# h2oiq_v4.net
KiCad netlist of a schematic drawn in EAGLE
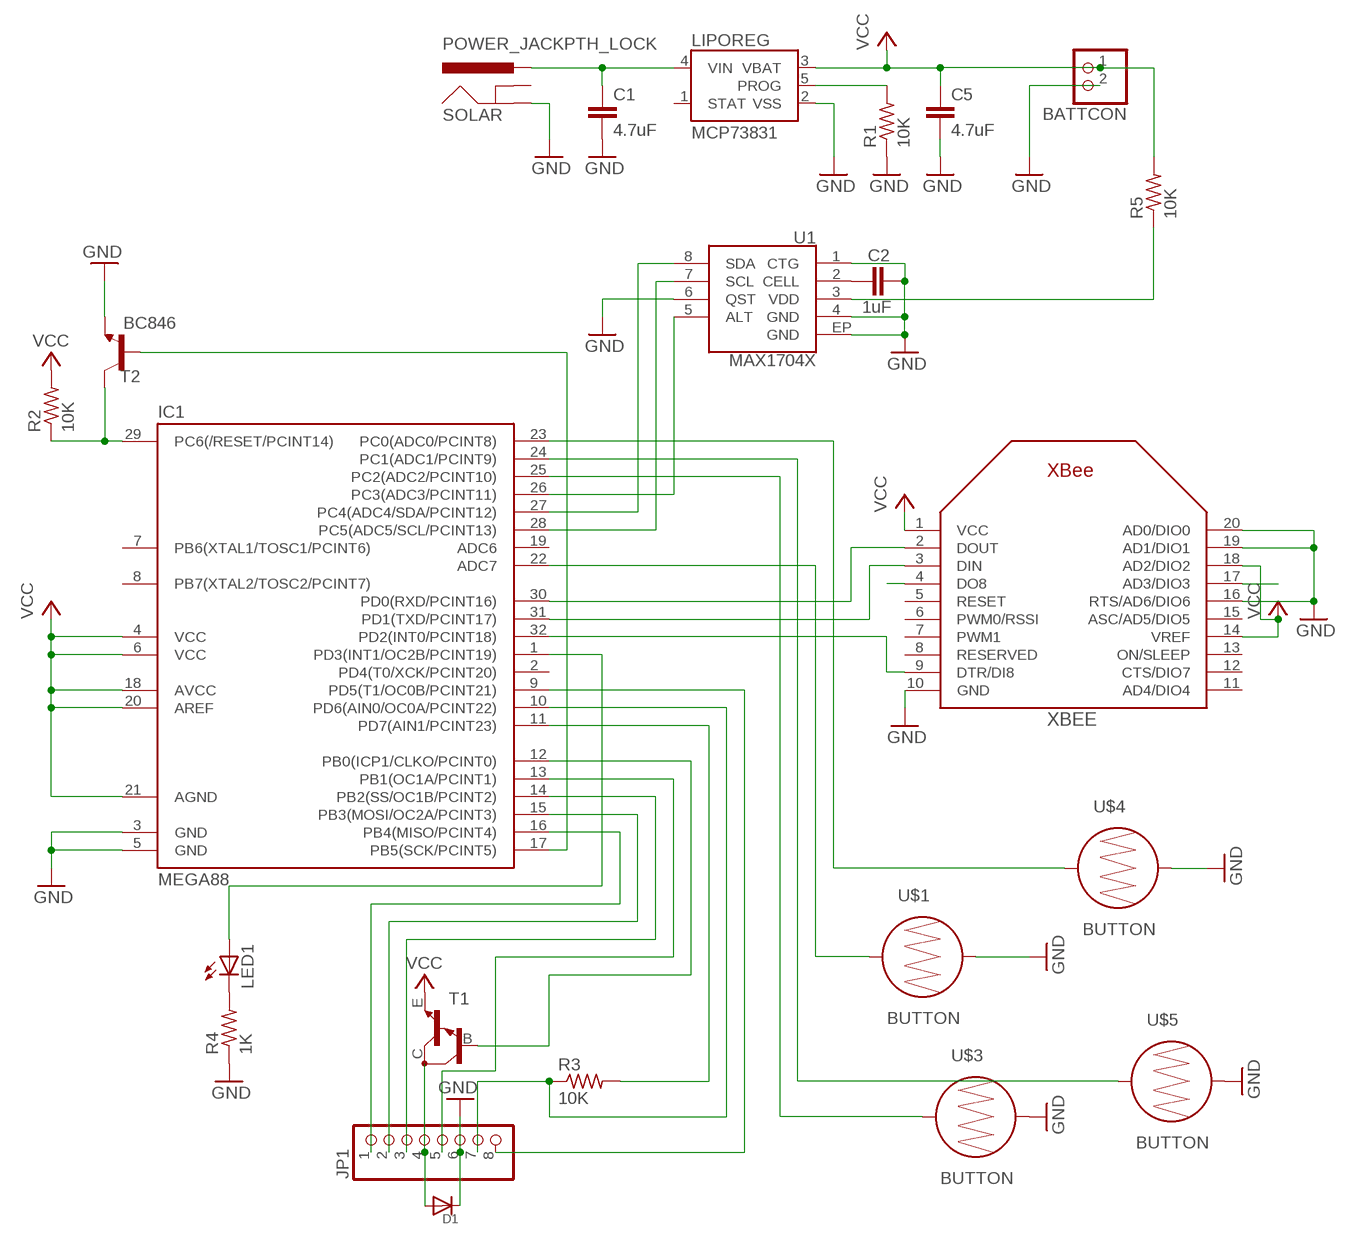
[diagram p0: schematic, sheet 1]

(export (version "E")
  (design (tool "Eeschema 10.0.6"))
  (components
    (comp (ref "BATTCON")
      (value "JST_2PIN-SMT")
      (footprint "eagle-import:JST-PH-2-SMT")
      (libsource (lib "eagle-import") (part "JST_2PIN-SMT"))
    )
    (comp (ref "C1")
      (value "4.7uF")
      (footprint "eagle-import:0402-CAP")
      (libsource (lib "eagle-import") (part "CAP0402-CAP"))
    )
    (comp (ref "C2")
      (value "1uF")
      (footprint "eagle-import:0402-CAP")
      (libsource (lib "eagle-import") (part "CAP0402-CAP"))
    )
    (comp (ref "C5")
      (value "4.7uF")
      (footprint "eagle-import:0402-CAP")
      (libsource (lib "eagle-import") (part "CAP0402-CAP"))
    )
    (comp (ref "D1")
      (value "DIODESMA")
      (footprint "eagle-import:SMADIODE")
      (libsource (lib "eagle-import") (part "DIODESMA"))
    )
    (comp (ref "IC1")
      (value "MEGA88")
      (footprint "eagle-import:MLF32")
      (libsource (lib "eagle-import") (part "MEGA48/88/168-MU"))
    )
    (comp (ref "JP1")
      (value "PINHD-1X8LOCK")
      (footprint "eagle-import:1X08-LOCK")
      (libsource (lib "eagle-import") (part "PINHD-1X8LOCK"))
    )
    (comp (ref "LED1")
      (value "LED")
      (footprint "eagle-import:SMARTLED-TTW")
      (libsource (lib "eagle-import") (part "LED"))
    )
    (comp (ref "LIPOREG")
      (value "MCP73831")
      (footprint "eagle-import:SOT23-5")
      (libsource (lib "eagle-import") (part "MCP73831"))
    )
    (comp (ref "R1")
      (value "10K")
      (footprint "eagle-import:R0603")
      (libsource (lib "eagle-import") (part "resistor_R-US_R0603"))
    )
    (comp (ref "R2")
      (value "10K")
      (footprint "eagle-import:R0603@1")
      (libsource (lib "eagle-import") (part "R-US_R0603"))
    )
    (comp (ref "R3")
      (value "10K")
      (footprint "eagle-import:R0603")
      (libsource (lib "eagle-import") (part "resistor_R-US_R0603"))
    )
    (comp (ref "R4")
      (value "1K")
      (footprint "eagle-import:R0603@1")
      (libsource (lib "eagle-import") (part "R-US_R0603"))
    )
    (comp (ref "R5")
      (value "10K")
      (footprint "eagle-import:R0603@1")
      (libsource (lib "eagle-import") (part "R-US_R0603"))
    )
    (comp (ref "SOLAR")
      (value "POWER_JACKPTH_LOCK")
      (footprint "eagle-import:POWER_JACK_PTH_LOCK")
      (libsource (lib "eagle-import") (part "POWER_JACKPTH_LOCK"))
    )
    (comp (ref "T1")
      (value "MMBTA13LT1-NPN_DARL-SOT23-BEC")
      (footprint "eagle-import:SOT23-BEC")
      (libsource (lib "eagle-import") (part "-NPN_DARL-SOT23-BECMMBTA13LT1"))
    )
    (comp (ref "T2")
      (value "BC846")
      (footprint "eagle-import:SOT23")
      (libsource (lib "eagle-import") (part "BC846"))
    )
    (comp (ref "U$1")
      (value "BUTTON")
      (footprint "eagle-import:BUTTON-CONDUCTIVE")
      (libsource (lib "eagle-import") (part "BUTTON-CONDUCTIVESMD"))
    )
    (comp (ref "U$3")
      (value "BUTTON")
      (footprint "eagle-import:BUTTON-CONDUCTIVE")
      (libsource (lib "eagle-import") (part "BUTTON-CONDUCTIVESMD"))
    )
    (comp (ref "U$4")
      (value "BUTTON")
      (footprint "eagle-import:BUTTON-CONDUCTIVE")
      (libsource (lib "eagle-import") (part "BUTTON-CONDUCTIVESMD"))
    )
    (comp (ref "U$5")
      (value "BUTTON")
      (footprint "eagle-import:BUTTON-CONDUCTIVE")
      (libsource (lib "eagle-import") (part "BUTTON-CONDUCTIVESMD"))
    )
    (comp (ref "U1")
      (value "MAX1704X")
      (footprint "eagle-import:TDFN-8")
      (libsource (lib "eagle-import") (part "MAX1704X"))
    )
    (comp (ref "XBEE")
      (value "XBEE")
      (footprint "eagle-import:XBEE")
      (libsource (lib "eagle-import") (part "XBEE"))
    )
  )
  (nets
    (net (code "1") (name "/MAX1704VDD") (class "Default")
      (node (ref "R5") (pin "1") (pinfunction "1_1") (pintype "passive"))
      (node (ref "U1") (pin "3") (pinfunction "VDD_3") (pintype "bidirectional"))
      (node (ref "XBEE") (pin "4") (pinfunction "DO8_4") (pintype "output"))
    )
    (net (code "2") (name "/SERVOACT") (class "Default")
      (node (ref "D1") (pin "A") (pinfunction "A_A") (pintype "passive"))
      (node (ref "JP1") (pin "4") (pinfunction "4_4") (pintype "passive"))
      (node (ref "T1") (pin "C") (pinfunction "C_C") (pintype "passive"))
      (node (ref "XBEE") (pin "17") (pinfunction "AD3/DIO3_17") (pintype "bidirectional"))
    )
    (net (code "3") (name "GND") (class "Default")
      (node (ref "BATTCON") (pin "2") (pinfunction "1_2") (pintype "passive"))
      (node (ref "C1") (pin "2") (pinfunction "2_2") (pintype "passive"))
      (node (ref "C2") (pin "2") (pinfunction "2_2") (pintype "passive"))
      (node (ref "C5") (pin "2") (pinfunction "2_2") (pintype "passive"))
      (node (ref "D1") (pin "C") (pinfunction "C_C") (pintype "passive"))
      (node (ref "IC1") (pin "3") (pinfunction "GND_3") (pintype "power_in"))
      (node (ref "IC1") (pin "5") (pinfunction "GND_5") (pintype "power_in"))
      (node (ref "JP1") (pin "6") (pinfunction "6_6") (pintype "passive"))
      (node (ref "LIPOREG") (pin "2") (pinfunction "VSS_2") (pintype "power_in"))
      (node (ref "R1") (pin "1") (pinfunction "1_1") (pintype "passive"))
      (node (ref "R4") (pin "1") (pinfunction "1_1") (pintype "passive"))
      (node (ref "SOLAR") (pin "GND") (pinfunction "GND_GND") (pintype "bidirectional"))
      (node (ref "T2") (pin "2") (pinfunction "E_2") (pintype "passive"))
      (node (ref "U$1") (pin "2") (pinfunction "2_2") (pintype "passive"))
      (node (ref "U$3") (pin "2") (pinfunction "2_2") (pintype "passive"))
      (node (ref "U$4") (pin "2") (pinfunction "2_2") (pintype "passive"))
      (node (ref "U$5") (pin "2") (pinfunction "2_2") (pintype "passive"))
      (node (ref "U1") (pin "1") (pinfunction "CTG_1") (pintype "bidirectional"))
      (node (ref "U1") (pin "4") (pinfunction "GND_4") (pintype "bidirectional"))
      (node (ref "U1") (pin "6") (pinfunction "QST_6") (pintype "bidirectional"))
      (node (ref "U1") (pin "EP") (pinfunction "GND_EP") (pintype "bidirectional"))
      (node (ref "XBEE") (pin "10") (pinfunction "GND_10") (pintype "power_in"))
      (node (ref "XBEE") (pin "16") (pinfunction "RTS/AD6/DIO6_16") (pintype "bidirectional"))
      (node (ref "XBEE") (pin "19") (pinfunction "AD1/DIO1_19") (pintype "bidirectional"))
      (node (ref "XBEE") (pin "20") (pinfunction "AD0/DIO0_20") (pintype "bidirectional"))
    )
    (net (code "4") (name "Net-(IC1-ADC7)") (class "Default")
      (node (ref "IC1") (pin "22") (pinfunction "ADC7_22") (pintype "passive"))
      (node (ref "U$1") (pin "1") (pinfunction "1_1") (pintype "passive"))
    )
    (net (code "5") (name "Net-(IC1-PB0(ICP1{slash}CLKO{slash}PCINT0))") (class "Default")
      (node (ref "IC1") (pin "12") (pinfunction "PB0(ICP1/CLKO/PCINT0)_12") (pintype "bidirectional"))
      (node (ref "T1") (pin "B") (pinfunction "B_B") (pintype "passive"))
    )
    (net (code "6") (name "Net-(IC1-PB1(OC1A{slash}PCINT1))") (class "Default")
      (node (ref "IC1") (pin "13") (pinfunction "PB1(OC1A/PCINT1)_13") (pintype "bidirectional"))
      (node (ref "JP1") (pin "5") (pinfunction "5_5") (pintype "passive"))
    )
    (net (code "7") (name "Net-(IC1-PB2(SS{slash}OC1B{slash}PCINT2))") (class "Default")
      (node (ref "IC1") (pin "14") (pinfunction "PB2(SS/OC1B/PCINT2)_14") (pintype "bidirectional"))
      (node (ref "JP1") (pin "3") (pinfunction "3_3") (pintype "passive"))
    )
    (net (code "8") (name "Net-(IC1-PB3(MOSI{slash}OC2A{slash}PCINT3))") (class "Default")
      (node (ref "IC1") (pin "15") (pinfunction "PB3(MOSI/OC2A/PCINT3)_15") (pintype "bidirectional"))
      (node (ref "JP1") (pin "2") (pinfunction "2_2") (pintype "passive"))
    )
    (net (code "9") (name "Net-(IC1-PB4(MISO{slash}PCINT4))") (class "Default")
      (node (ref "IC1") (pin "16") (pinfunction "PB4(MISO/PCINT4)_16") (pintype "bidirectional"))
      (node (ref "JP1") (pin "1") (pinfunction "1_1") (pintype "passive"))
    )
    (net (code "10") (name "Net-(IC1-PB5(SCK{slash}PCINT5))") (class "Default")
      (node (ref "IC1") (pin "17") (pinfunction "PB5(SCK/PCINT5)_17") (pintype "bidirectional"))
      (node (ref "T2") (pin "1") (pinfunction "B_1") (pintype "passive"))
    )
    (net (code "11") (name "Net-(IC1-PC0(ADC0{slash}PCINT8))") (class "Default")
      (node (ref "IC1") (pin "23") (pinfunction "PC0(ADC0/PCINT8)_23") (pintype "bidirectional"))
      (node (ref "U$4") (pin "1") (pinfunction "1_1") (pintype "passive"))
    )
    (net (code "12") (name "Net-(IC1-PC1(ADC1{slash}PCINT9))") (class "Default")
      (node (ref "IC1") (pin "24") (pinfunction "PC1(ADC1/PCINT9)_24") (pintype "bidirectional"))
      (node (ref "U$5") (pin "1") (pinfunction "1_1") (pintype "passive"))
    )
    (net (code "13") (name "Net-(IC1-PC2(ADC2{slash}PCINT10))") (class "Default")
      (node (ref "IC1") (pin "25") (pinfunction "PC2(ADC2/PCINT10)_25") (pintype "bidirectional"))
      (node (ref "U$3") (pin "1") (pinfunction "1_1") (pintype "passive"))
    )
    (net (code "14") (name "Net-(IC1-PC3(ADC3{slash}PCINT11))") (class "Default")
      (node (ref "IC1") (pin "26") (pinfunction "PC3(ADC3/PCINT11)_26") (pintype "bidirectional"))
      (node (ref "U1") (pin "5") (pinfunction "ALT_5") (pintype "bidirectional"))
    )
    (net (code "15") (name "Net-(IC1-PC4(ADC4{slash}SDA{slash}PCINT12))") (class "Default")
      (node (ref "IC1") (pin "27") (pinfunction "PC4(ADC4/SDA/PCINT12)_27") (pintype "bidirectional"))
      (node (ref "U1") (pin "8") (pinfunction "SDA_8") (pintype "bidirectional"))
    )
    (net (code "16") (name "Net-(IC1-PC5(ADC5{slash}SCL{slash}PCINT13))") (class "Default")
      (node (ref "IC1") (pin "28") (pinfunction "PC5(ADC5/SCL/PCINT13)_28") (pintype "bidirectional"))
      (node (ref "U1") (pin "7") (pinfunction "SCL_7") (pintype "bidirectional"))
    )
    (net (code "17") (name "Net-(IC1-PC6({slash}RESET{slash}PCINT14))") (class "Default")
      (node (ref "IC1") (pin "29") (pinfunction "PC6(/RESET/PCINT14)_29") (pintype "bidirectional"))
      (node (ref "R2") (pin "1") (pinfunction "1_1") (pintype "passive"))
      (node (ref "T2") (pin "3") (pinfunction "C_3") (pintype "passive"))
    )
    (net (code "18") (name "Net-(IC1-PD0(RXD{slash}PCINT16))") (class "Default")
      (node (ref "IC1") (pin "30") (pinfunction "PD0(RXD/PCINT16)_30") (pintype "bidirectional"))
      (node (ref "XBEE") (pin "2") (pinfunction "DOUT_2") (pintype "output"))
    )
    (net (code "19") (name "Net-(IC1-PD1(TXD{slash}PCINT17))") (class "Default")
      (node (ref "IC1") (pin "31") (pinfunction "PD1(TXD/PCINT17)_31") (pintype "bidirectional"))
      (node (ref "XBEE") (pin "3") (pinfunction "DIN_3") (pintype "input"))
    )
    (net (code "20") (name "Net-(IC1-PD2(INT0{slash}PCINT18))") (class "Default")
      (node (ref "IC1") (pin "32") (pinfunction "PD2(INT0/PCINT18)_32") (pintype "bidirectional"))
      (node (ref "XBEE") (pin "9") (pinfunction "DTR/DI8_9") (pintype "input"))
    )
    (net (code "21") (name "Net-(IC1-PD3(INT1{slash}OC2B{slash}PCINT19))") (class "Default")
      (node (ref "IC1") (pin "1") (pinfunction "PD3(INT1/OC2B/PCINT19)_1") (pintype "bidirectional"))
      (node (ref "LED1") (pin "A@1") (pinfunction "A_A@1") (pintype "passive"))
    )
    (net (code "22") (name "Net-(IC1-PD5(T1{slash}OC0B{slash}PCINT21))") (class "Default")
      (node (ref "IC1") (pin "9") (pinfunction "PD5(T1/OC0B/PCINT21)_9") (pintype "bidirectional"))
      (node (ref "JP1") (pin "8") (pinfunction "8_8") (pintype "passive"))
    )
    (net (code "23") (name "Net-(IC1-PD6(AIN0{slash}OC0A{slash}PCINT22))") (class "Default")
      (node (ref "IC1") (pin "10") (pinfunction "PD6(AIN0/OC0A/PCINT22)_10") (pintype "bidirectional"))
      (node (ref "JP1") (pin "7") (pinfunction "7_7") (pintype "passive"))
      (node (ref "R3") (pin "1") (pinfunction "1_1") (pintype "passive"))
    )
    (net (code "24") (name "Net-(IC1-PD7(AIN1{slash}PCINT23))") (class "Default")
      (node (ref "IC1") (pin "11") (pinfunction "PD7(AIN1/PCINT23)_11") (pintype "bidirectional"))
      (node (ref "R3") (pin "2") (pinfunction "2_2") (pintype "passive"))
    )
    (net (code "25") (name "Net-(LED1-C)") (class "Default")
      (node (ref "LED1") (pin "C@1") (pinfunction "C_C@1") (pintype "passive"))
      (node (ref "R4") (pin "2") (pinfunction "2_2") (pintype "passive"))
    )
    (net (code "26") (name "Net-(LIPOREG-PROG)") (class "Default")
      (node (ref "LIPOREG") (pin "5") (pinfunction "PROG_5") (pintype "input"))
      (node (ref "R1") (pin "2") (pinfunction "2_2") (pintype "passive"))
    )
    (net (code "27") (name "Net-(LIPOREG-VIN)") (class "Default")
      (node (ref "C1") (pin "1") (pinfunction "1_1") (pintype "passive"))
      (node (ref "LIPOREG") (pin "4") (pinfunction "VIN_4") (pintype "power_in"))
      (node (ref "SOLAR") (pin "PWR") (pinfunction "PWR_PWR") (pintype "bidirectional"))
    )
    (net (code "28") (name "Net-(U1-CELL)") (class "Default")
      (node (ref "C2") (pin "1") (pinfunction "1_1") (pintype "passive"))
      (node (ref "U1") (pin "2") (pinfunction "CELL_2") (pintype "bidirectional"))
    )
    (net (code "29") (name "VCC") (class "Default")
      (node (ref "BATTCON") (pin "1") (pinfunction "2_1") (pintype "passive"))
      (node (ref "C5") (pin "1") (pinfunction "1_1") (pintype "passive"))
      (node (ref "IC1") (pin "18") (pinfunction "AVCC_18") (pintype "passive"))
      (node (ref "IC1") (pin "20") (pinfunction "AREF_20") (pintype "passive"))
      (node (ref "IC1") (pin "21") (pinfunction "AGND_21") (pintype "power_in"))
      (node (ref "IC1") (pin "4") (pinfunction "VCC_4") (pintype "power_in"))
      (node (ref "IC1") (pin "6") (pinfunction "VCC_6") (pintype "power_in"))
      (node (ref "LIPOREG") (pin "3") (pinfunction "VBAT_3") (pintype "power_in"))
      (node (ref "R2") (pin "2") (pinfunction "2_2") (pintype "passive"))
      (node (ref "R5") (pin "2") (pinfunction "2_2") (pintype "passive"))
      (node (ref "T1") (pin "E") (pinfunction "E_E") (pintype "passive"))
      (node (ref "XBEE") (pin "1") (pinfunction "VCC_1") (pintype "power_in"))
      (node (ref "XBEE") (pin "14") (pinfunction "VREF_14") (pintype "input"))
      (node (ref "XBEE") (pin "18") (pinfunction "AD2/DIO2_18") (pintype "bidirectional"))
    )
    (net (code "30") (name "unconnected-(IC1-ADC6-Pad19)") (class "Default")
      (node (ref "IC1") (pin "19") (pinfunction "ADC6_19") (pintype "passive"))
    )
    (net (code "31") (name "unconnected-(IC1-PB6(XTAL1{slash}TOSC1{slash}PCINT6)-Pad7)") (class "Default")
      (node (ref "IC1") (pin "7") (pinfunction "PB6(XTAL1/TOSC1/PCINT6)_7") (pintype "bidirectional"))
    )
    (net (code "32") (name "unconnected-(IC1-PB7(XTAL2{slash}TOSC2{slash}PCINT7)-Pad8)") (class "Default")
      (node (ref "IC1") (pin "8") (pinfunction "PB7(XTAL2/TOSC2/PCINT7)_8") (pintype "bidirectional"))
    )
    (net (code "33") (name "unconnected-(IC1-PD4(T0{slash}XCK{slash}PCINT20)-Pad2)") (class "Default")
      (node (ref "IC1") (pin "2") (pinfunction "PD4(T0/XCK/PCINT20)_2") (pintype "bidirectional"))
    )
    (net (code "34") (name "unconnected-(LIPOREG-STAT-Pad1)") (class "Default")
      (node (ref "LIPOREG") (pin "1") (pinfunction "STAT_1") (pintype "output"))
    )
    (net (code "35") (name "unconnected-(SOLAR-PadGNDBREAK)") (class "Default")
      (node (ref "SOLAR") (pin "GNDBREAK") (pinfunction "GNDBREAK_GNDBREAK") (pintype "bidirectional"))
    )
    (net (code "36") (name "unconnected-(XBEE-AD4{slash}DIO4-Pad11)") (class "Default")
      (node (ref "XBEE") (pin "11") (pinfunction "AD4/DIO4_11") (pintype "bidirectional"))
    )
    (net (code "37") (name "unconnected-(XBEE-ASC{slash}AD5{slash}DIO5-Pad15)") (class "Default")
      (node (ref "XBEE") (pin "15") (pinfunction "ASC/AD5/DIO5_15") (pintype "bidirectional"))
    )
    (net (code "38") (name "unconnected-(XBEE-CTS{slash}DIO7-Pad12)") (class "Default")
      (node (ref "XBEE") (pin "12") (pinfunction "CTS/DIO7_12") (pintype "bidirectional"))
    )
    (net (code "39") (name "unconnected-(XBEE-ON{slash}SLEEP-Pad13)") (class "Default")
      (node (ref "XBEE") (pin "13") (pinfunction "ON/SLEEP_13") (pintype "output"))
    )
    (net (code "40") (name "unconnected-(XBEE-PWM0{slash}RSSI-Pad6)") (class "Default")
      (node (ref "XBEE") (pin "6") (pinfunction "PWM0/RSSI_6") (pintype "output"))
    )
    (net (code "41") (name "unconnected-(XBEE-PWM1-Pad7)") (class "Default")
      (node (ref "XBEE") (pin "7") (pinfunction "PWM1_7") (pintype "output"))
    )
    (net (code "42") (name "unconnected-(XBEE-RESERVED-Pad8)") (class "Default")
      (node (ref "XBEE") (pin "8") (pinfunction "RESERVED_8") (pintype "no_connect"))
    )
    (net (code "43") (name "unconnected-(XBEE-RESET-Pad5)") (class "Default")
      (node (ref "XBEE") (pin "5") (pinfunction "RESET_5") (pintype "input"))
    )
  )
)
